# Quectel_BC260Y-CN_SCH_Part_AD_V1_0.net
KiCad netlist of a schematic drawn in Altium Designer
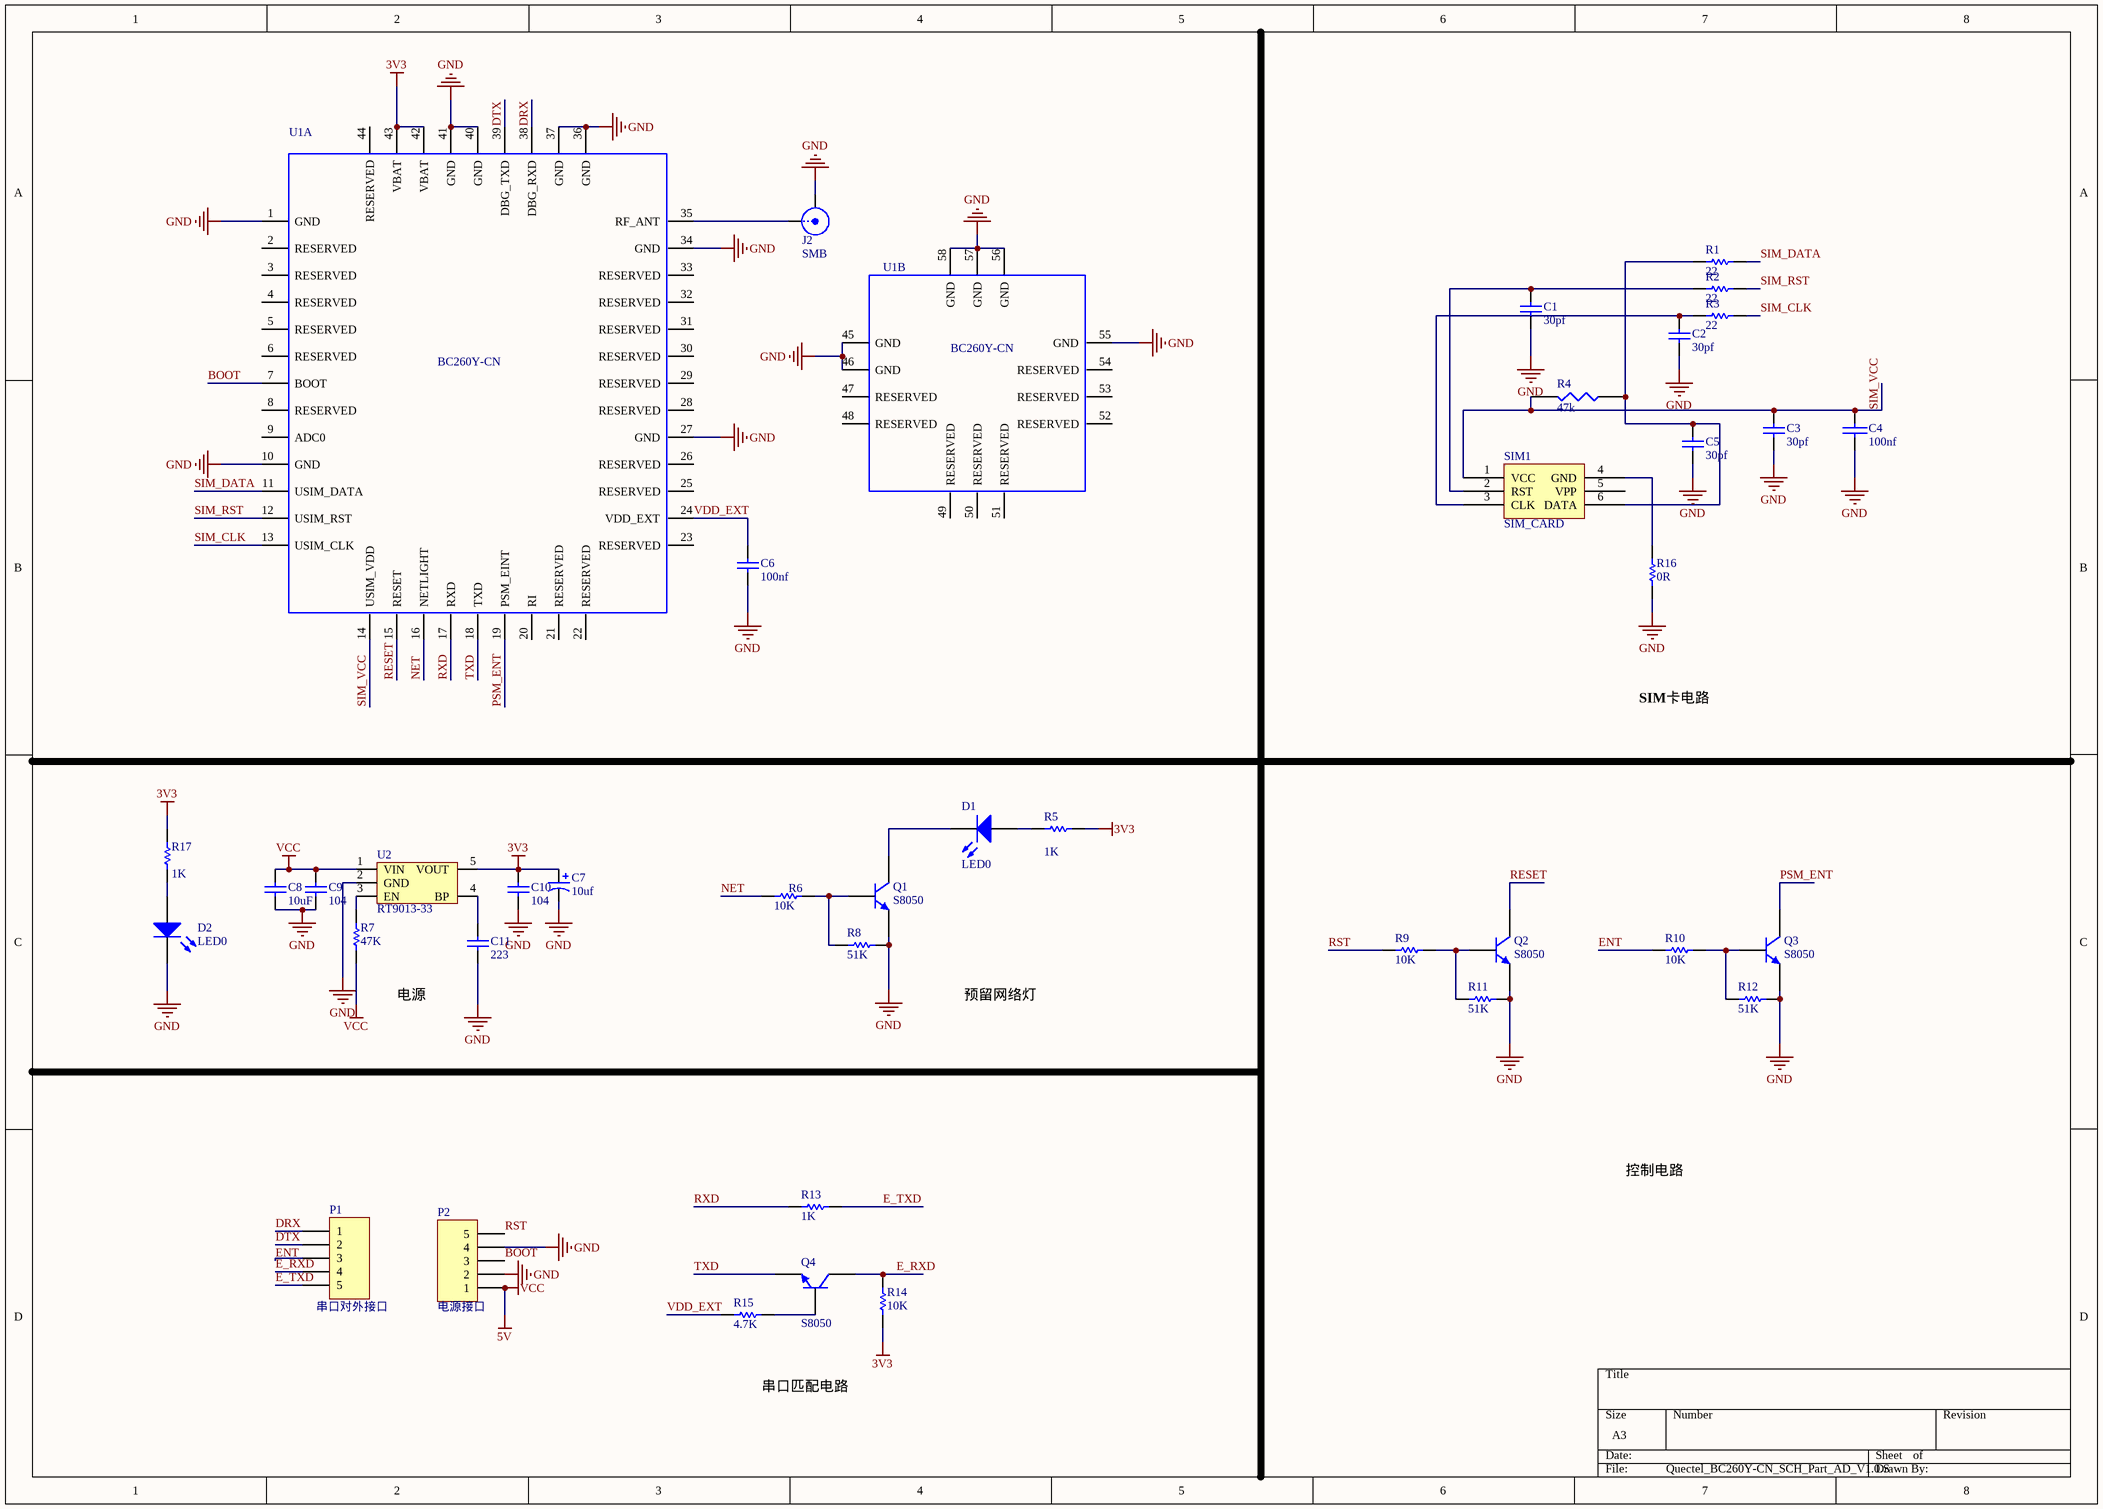
[diagram p0: Quectel_BC260Y-CN_SCH_Part_AD_V1.0.SchDoc]

(export (version "E")
  (design (tool "Eeschema 10.0.6"))
  (components
    (comp (ref "C1")
      (value "30pf")
      (footprint "0603A")
      (description "Capacitor")
      (fields (field (name "PUBLISHER") "Altium Limited"))
      (libsource (lib "Miscellaneous Devices") (part "Cap"))
    )
    (comp (ref "C2")
      (value "30pf")
      (footprint "0603A")
      (description "Capacitor")
      (fields (field (name "PUBLISHER") "Altium Limited"))
      (libsource (lib "Miscellaneous Devices") (part "Cap"))
    )
    (comp (ref "C3")
      (value "30pf")
      (footprint "0603A")
      (description "Capacitor")
      (fields (field (name "PUBLISHER") "Altium Limited"))
      (libsource (lib "Miscellaneous Devices") (part "Cap"))
    )
    (comp (ref "C4")
      (value "100nf")
      (footprint "0603A")
      (description "Capacitor")
      (libsource (lib "Miscellaneous Devices") (part "CAP"))
    )
    (comp (ref "C5")
      (value "30pf")
      (footprint "0603A")
      (description "Capacitor")
      (fields (field (name "PUBLISHER") "Altium Limited"))
      (libsource (lib "Miscellaneous Devices") (part "Cap"))
    )
    (comp (ref "C6")
      (value "100nf")
      (footprint "0603a")
      (description "Capacitor")
      (fields (field (name "PUBLISHER") "Altium Limited"))
      (libsource (lib "Miscellaneous Devices") (part "Cap"))
    )
    (comp (ref "C7") (value "10uf") (footprint "1206") (libsource (lib "*") (part "CAP-POL")))
    (comp (ref "C8")
      (value "10uF")
      (footprint "1206")
      (description "Capacitor")
      (fields (field (name "PUBLISHER") "Altium Limited"))
      (libsource (lib "Miscellaneous Devices") (part "Cap"))
    )
    (comp (ref "C9")
      (value "104")
      (footprint "0603a")
      (description "Capacitor")
      (fields (field (name "PUBLISHER") "Altium Limited"))
      (libsource (lib "Miscellaneous Devices") (part "Cap"))
    )
    (comp (ref "C10")
      (value "104")
      (footprint "0603a")
      (description "Capacitor")
      (fields (field (name "PUBLISHER") "Altium Limited"))
      (libsource (lib "Miscellaneous Devices") (part "Cap"))
    )
    (comp (ref "C11")
      (value "223")
      (footprint "0603a")
      (description "Capacitor")
      (fields (field (name "PUBLISHER") "Altium Limited"))
      (libsource (lib "Miscellaneous Devices") (part "Cap"))
    )
    (comp (ref "D1")
      (value "LED0")
      (footprint "0603led")
      (description "Typical INFRARED GaAs LED")
      (fields (field (name "PUBLISHER") "Altium Limited"))
      (libsource (lib "Miscellaneous Devices") (part "LED0"))
    )
    (comp (ref "D2")
      (value "LED0")
      (footprint "0603led")
      (description "Typical INFRARED GaAs LED")
      (fields (field (name "PUBLISHER") "Altium Limited"))
      (libsource (lib "Miscellaneous Devices") (part "LED0"))
    )
    (comp (ref "J2")
      (value "SMB")
      (footprint "ipex")
      (description "SMB Straight Connector")
      (fields (field (name "PUBLISHER") "Altium Limited"))
      (libsource (lib "Miscellaneous Connectors") (part "SMB"))
    )
    (comp (ref "P1")
      (value "串口对外接口")
      (footprint "HDR1X5")
      (description "Header, 5-Pin")
      (fields (field (name "PUBLISHER") "Altium Limited"))
      (libsource (lib "") (part "Header 5_1"))
    )
    (comp (ref "P2")
      (value "电源接口")
      (footprint "HDR1X5")
      (description "Header, 5-Pin")
      (fields (field (name "PUBLISHER") "Altium Limited"))
      (libsource (lib "Miscellaneous Connectors") (part "Header 5"))
    )
    (comp (ref "Q1")
      (value "S8050")
      (footprint "s8550")
      (description "NPN General Purpose Amplifier")
      (fields (field (name "PUBLISHER") "Altium Limited"))
      (libsource (lib "Miscellaneous Devices") (part "2N3904"))
    )
    (comp (ref "Q2")
      (value "S8050")
      (footprint "s8550")
      (description "NPN General Purpose Amplifier")
      (fields (field (name "PUBLISHER") "Altium Limited"))
      (libsource (lib "Miscellaneous Devices") (part "2N3904"))
    )
    (comp (ref "Q3")
      (value "S8050")
      (footprint "s8550")
      (description "NPN General Purpose Amplifier")
      (fields (field (name "PUBLISHER") "Altium Limited"))
      (libsource (lib "Miscellaneous Devices") (part "2N3904"))
    )
    (comp (ref "Q4")
      (value "S8050")
      (footprint "S8550")
      (description "NPN General Purpose Amplifier")
      (fields (field (name "PUBLISHER") "Altium Limited"))
      (libsource (lib "Miscellaneous Devices") (part "2N3904"))
    )
    (comp (ref "R1")
      (value "22")
      (footprint "0603A")
      (description "Resistor")
      (fields (field (name "PUBLISHER") "Altium Limited"))
      (libsource (lib "Miscellaneous Devices") (part "Res1"))
    )
    (comp (ref "R2")
      (value "22")
      (footprint "0603A")
      (description "Resistor")
      (fields (field (name "PUBLISHER") "Altium Limited"))
      (libsource (lib "Miscellaneous Devices") (part "Res1"))
    )
    (comp (ref "R3")
      (value "22")
      (footprint "0603A")
      (description "Resistor")
      (fields (field (name "PUBLISHER") "Altium Limited"))
      (libsource (lib "Miscellaneous Devices") (part "Res1"))
    )
    (comp (ref "R4")
      (value "47k")
      (footprint "0603A")
      (libsource (lib "Miscellaneous Devices") (part "RES1"))
    )
    (comp (ref "R5")
      (value "1K")
      (footprint "0603a")
      (description "Semiconductor Resistor")
      (fields (field (name "PUBLISHER") "Altium Limited"))
      (libsource (lib "Miscellaneous Devices") (part "Res Semi"))
    )
    (comp (ref "R6")
      (value "10K")
      (footprint "0603A")
      (description "Resistor")
      (fields (field (name "PUBLISHER") "Altium Limited"))
      (libsource (lib "Miscellaneous Devices") (part "Res1"))
    )
    (comp (ref "R7")
      (value "47K")
      (footprint "0603a")
      (description "Resistor")
      (fields (field (name "PUBLISHER") "Altium Limited"))
      (libsource (lib "Miscellaneous Devices") (part "Res1"))
    )
    (comp (ref "R8")
      (value "51K")
      (footprint "0603A")
      (description "Resistor")
      (fields (field (name "PUBLISHER") "Altium Limited"))
      (libsource (lib "Miscellaneous Devices") (part "Res1"))
    )
    (comp (ref "R9")
      (value "10K")
      (footprint "0603A")
      (description "Resistor")
      (fields (field (name "PUBLISHER") "Altium Limited"))
      (libsource (lib "Miscellaneous Devices") (part "Res1"))
    )
    (comp (ref "R10")
      (value "10K")
      (footprint "0603A")
      (description "Resistor")
      (fields (field (name "PUBLISHER") "Altium Limited"))
      (libsource (lib "Miscellaneous Devices") (part "Res1"))
    )
    (comp (ref "R11")
      (value "51K")
      (footprint "0603A")
      (description "Resistor")
      (fields (field (name "PUBLISHER") "Altium Limited"))
      (libsource (lib "Miscellaneous Devices") (part "Res1"))
    )
    (comp (ref "R12")
      (value "51K")
      (footprint "0603A")
      (description "Resistor")
      (fields (field (name "PUBLISHER") "Altium Limited"))
      (libsource (lib "Miscellaneous Devices") (part "Res1"))
    )
    (comp (ref "R13")
      (value "1K")
      (footprint "0603A")
      (description "Resistor")
      (fields (field (name "PUBLISHER") "Altium Limited"))
      (libsource (lib "Miscellaneous Devices") (part "Res1"))
    )
    (comp (ref "R14")
      (value "10K")
      (footprint "0603A")
      (description "Resistor")
      (fields (field (name "PUBLISHER") "Altium Limited"))
      (libsource (lib "Miscellaneous Devices") (part "Res1"))
    )
    (comp (ref "R15")
      (value "4.7K")
      (footprint "0603A")
      (description "Resistor")
      (fields (field (name "PUBLISHER") "Altium Limited"))
      (libsource (lib "Miscellaneous Devices") (part "Res1"))
    )
    (comp (ref "R16")
      (value "0R")
      (footprint "0603A")
      (description "Resistor")
      (fields (field (name "PUBLISHER") "Altium Limited"))
      (libsource (lib "Miscellaneous Devices") (part "Res1"))
    )
    (comp (ref "R17")
      (value "1K")
      (footprint "0603a")
      (description "Semiconductor Resistor")
      (fields (field (name "PUBLISHER") "Altium Limited"))
      (libsource (lib "Miscellaneous Devices") (part "Res Semi"))
    )
    (comp (ref "SIM1")
      (value "SIM_CARD")
      (footprint "microSIMauto")
      (libsource (lib "M26_SCH_140527") (part "SIM_CARD"))
    )
    (comp (ref "U1")
      (value "BC260Y-CN")
      (footprint "bc260y")
      (fields (field (name "MANUFACTURER") "QUECTEL"))
      (libsource (lib "BC260Y-CN") (part "BC260Y-CN"))
    )
    (comp (ref "U2")
      (value "RT9013-33")
      (footprint "SOT-23-5")
      (description "3.3V超低压差LDO")
      (libsource (lib "BC05") (part "RT9193-33"))
    )
  )
  (nets
    (net (code "1") (name "/BOOT") (class "Default")
      (node (ref "P2") (pin "3") (pinfunction "3_3") (pintype "passive"))
      (node (ref "U1") (pin "7") (pinfunction "BOOT_7") (pintype "passive"))
    )
    (net (code "2") (name "/DRX") (class "Default")
      (node (ref "P1") (pin "1") (pinfunction "1_1") (pintype "passive"))
      (node (ref "U1") (pin "38") (pinfunction "DBG_RXD_38") (pintype "passive"))
    )
    (net (code "3") (name "/DTX") (class "Default")
      (node (ref "P1") (pin "2") (pinfunction "2_2") (pintype "passive"))
      (node (ref "U1") (pin "39") (pinfunction "DBG_TXD_39") (pintype "passive"))
    )
    (net (code "4") (name "/ENT") (class "Default")
      (node (ref "P1") (pin "3") (pinfunction "3_3") (pintype "passive"))
      (node (ref "R10") (pin "1") (pinfunction "1_1") (pintype "passive"))
    )
    (net (code "5") (name "/E_RXD") (class "Default")
      (node (ref "P1") (pin "4") (pinfunction "4_4") (pintype "passive"))
      (node (ref "Q4") (pin "3") (pinfunction "C_3") (pintype "passive"))
      (node (ref "R14") (pin "2") (pinfunction "2_2") (pintype "passive"))
    )
    (net (code "6") (name "/E_TXD") (class "Default")
      (node (ref "P1") (pin "5") (pinfunction "5_5") (pintype "passive"))
      (node (ref "R13") (pin "2") (pinfunction "2_2") (pintype "passive"))
    )
    (net (code "7") (name "/NET") (class "Default")
      (node (ref "R6") (pin "1") (pinfunction "1_1") (pintype "passive"))
      (node (ref "U1") (pin "16") (pinfunction "NETLIGHT_16") (pintype "passive"))
    )
    (net (code "8") (name "/PSM_ENT") (class "Default")
      (node (ref "Q3") (pin "3") (pinfunction "C_3") (pintype "passive"))
      (node (ref "U1") (pin "19") (pinfunction "PSM_EINT_19") (pintype "passive"))
    )
    (net (code "9") (name "/RESET") (class "Default")
      (node (ref "Q2") (pin "3") (pinfunction "C_3") (pintype "passive"))
      (node (ref "U1") (pin "15") (pinfunction "RESET_15") (pintype "passive"))
    )
    (net (code "10") (name "/RST") (class "Default")
      (node (ref "P2") (pin "5") (pinfunction "5_5") (pintype "passive"))
      (node (ref "R9") (pin "1") (pinfunction "1_1") (pintype "passive"))
    )
    (net (code "11") (name "/RXD") (class "Default")
      (node (ref "R13") (pin "1") (pinfunction "1_1") (pintype "passive"))
      (node (ref "U1") (pin "17") (pinfunction "RXD_17") (pintype "passive"))
    )
    (net (code "12") (name "/SIM_CLK") (class "Default")
      (node (ref "R3") (pin "1") (pinfunction "1_1") (pintype "passive"))
      (node (ref "U1") (pin "13") (pinfunction "USIM_CLK_13") (pintype "passive"))
    )
    (net (code "13") (name "/SIM_DATA") (class "Default")
      (node (ref "R1") (pin "1") (pinfunction "1_1") (pintype "passive"))
      (node (ref "U1") (pin "11") (pinfunction "USIM_DATA_11") (pintype "passive"))
    )
    (net (code "14") (name "/SIM_RST") (class "Default")
      (node (ref "R2") (pin "1") (pinfunction "1_1") (pintype "passive"))
      (node (ref "U1") (pin "12") (pinfunction "USIM_RST_12") (pintype "passive"))
    )
    (net (code "15") (name "/SIM_VCC") (class "Default")
      (node (ref "C3") (pin "2") (pinfunction "2_2") (pintype "passive"))
      (node (ref "C4") (pin "1") (pinfunction "1_1") (pintype "passive"))
      (node (ref "R4") (pin "2") (pinfunction "2_2") (pintype "passive"))
      (node (ref "SIM1") (pin "1") (pinfunction "VCC_1") (pintype "passive"))
      (node (ref "U1") (pin "14") (pinfunction "USIM_VDD_14") (pintype "passive"))
    )
    (net (code "16") (name "/TXD") (class "Default")
      (node (ref "Q4") (pin "1") (pinfunction "E_1") (pintype "passive"))
      (node (ref "U1") (pin "18") (pinfunction "TXD_18") (pintype "passive"))
    )
    (net (code "17") (name "/VDD_EXT") (class "Default")
      (node (ref "C6") (pin "2") (pinfunction "2_2") (pintype "passive"))
      (node (ref "R15") (pin "1") (pinfunction "1_1") (pintype "passive"))
      (node (ref "U1") (pin "24") (pinfunction "VDD_EXT_24") (pintype "passive"))
    )
    (net (code "18") (name "3V3") (class "Default")
      (node (ref "C10") (pin "1") (pinfunction "1_1") (pintype "passive"))
      (node (ref "C7") (pin "1") (pinfunction "+_1") (pintype "passive"))
      (node (ref "R14") (pin "1") (pinfunction "1_1") (pintype "passive"))
      (node (ref "R17") (pin "1") (pinfunction "1_1") (pintype "passive"))
      (node (ref "R5") (pin "1") (pinfunction "1_1") (pintype "passive"))
      (node (ref "U1") (pin "42") (pinfunction "VBAT_42") (pintype "passive"))
      (node (ref "U1") (pin "43") (pinfunction "VBAT_43") (pintype "passive"))
      (node (ref "U2") (pin "5") (pinfunction "VOUT_5") (pintype "passive"))
    )
    (net (code "19") (name "5V") (class "Default")
      (node (ref "C8") (pin "2") (pinfunction "2_2") (pintype "passive"))
      (node (ref "C9") (pin "2") (pinfunction "2_2") (pintype "passive"))
      (node (ref "P2") (pin "1") (pinfunction "1_1") (pintype "passive"))
      (node (ref "R7") (pin "1") (pinfunction "1_1") (pintype "passive"))
      (node (ref "U2") (pin "1") (pinfunction "VIN_1") (pintype "passive"))
    )
    (net (code "20") (name "GND") (class "Default")
      (node (ref "C1") (pin "1") (pinfunction "1_1") (pintype "passive"))
      (node (ref "C10") (pin "2") (pinfunction "2_2") (pintype "passive"))
      (node (ref "C11") (pin "2") (pinfunction "2_2") (pintype "passive"))
      (node (ref "C2") (pin "1") (pinfunction "1_1") (pintype "passive"))
      (node (ref "C3") (pin "1") (pinfunction "1_1") (pintype "passive"))
      (node (ref "C4") (pin "2") (pinfunction "2_2") (pintype "passive"))
      (node (ref "C5") (pin "1") (pinfunction "1_1") (pintype "passive"))
      (node (ref "C6") (pin "1") (pinfunction "1_1") (pintype "passive"))
      (node (ref "C7") (pin "2") (pinfunction "-_2") (pintype "passive"))
      (node (ref "C8") (pin "1") (pinfunction "1_1") (pintype "passive"))
      (node (ref "C9") (pin "1") (pinfunction "1_1") (pintype "passive"))
      (node (ref "D2") (pin "2") (pinfunction "K_2") (pintype "passive"))
      (node (ref "J2") (pin "2") (pinfunction "Y_2") (pintype "passive"))
      (node (ref "P2") (pin "2") (pinfunction "2_2") (pintype "passive"))
      (node (ref "P2") (pin "4") (pinfunction "4_4") (pintype "passive"))
      (node (ref "Q1") (pin "1") (pinfunction "E_1") (pintype "passive"))
      (node (ref "Q2") (pin "1") (pinfunction "E_1") (pintype "passive"))
      (node (ref "Q3") (pin "1") (pinfunction "E_1") (pintype "passive"))
      (node (ref "R11") (pin "2") (pinfunction "2_2") (pintype "passive"))
      (node (ref "R12") (pin "2") (pinfunction "2_2") (pintype "passive"))
      (node (ref "R16") (pin "1") (pinfunction "1_1") (pintype "passive"))
      (node (ref "R8") (pin "2") (pinfunction "2_2") (pintype "passive"))
      (node (ref "U1") (pin "1") (pinfunction "GND_1") (pintype "passive"))
      (node (ref "U1") (pin "10") (pinfunction "GND_10") (pintype "passive"))
      (node (ref "U1") (pin "27") (pinfunction "GND_27") (pintype "passive"))
      (node (ref "U1") (pin "34") (pinfunction "GND_34") (pintype "passive"))
      (node (ref "U1") (pin "36") (pinfunction "GND_36") (pintype "passive"))
      (node (ref "U1") (pin "37") (pinfunction "GND_37") (pintype "passive"))
      (node (ref "U1") (pin "40") (pinfunction "GND_40") (pintype "passive"))
      (node (ref "U1") (pin "41") (pinfunction "GND_41") (pintype "passive"))
      (node (ref "U1") (pin "45") (pinfunction "GND_45") (pintype "passive"))
      (node (ref "U1") (pin "46") (pinfunction "GND_46") (pintype "passive"))
      (node (ref "U1") (pin "55") (pinfunction "GND_55") (pintype "passive"))
      (node (ref "U1") (pin "56") (pinfunction "GND_56") (pintype "passive"))
      (node (ref "U1") (pin "57") (pinfunction "GND_57") (pintype "passive"))
      (node (ref "U1") (pin "58") (pinfunction "GND_58") (pintype "passive"))
      (node (ref "U2") (pin "2") (pinfunction "GND_2") (pintype "passive"))
    )
    (net (code "21") (name "Net-(D1-A)") (class "Default")
      (node (ref "D1") (pin "1") (pinfunction "A_1") (pintype "passive"))
      (node (ref "R5") (pin "2") (pinfunction "2_2") (pintype "passive"))
    )
    (net (code "22") (name "Net-(D1-K)") (class "Default")
      (node (ref "D1") (pin "2") (pinfunction "K_2") (pintype "passive"))
      (node (ref "Q1") (pin "3") (pinfunction "C_3") (pintype "passive"))
    )
    (net (code "23") (name "Net-(D2-A)") (class "Default")
      (node (ref "D2") (pin "1") (pinfunction "A_1") (pintype "passive"))
      (node (ref "R17") (pin "2") (pinfunction "2_2") (pintype "passive"))
    )
    (net (code "24") (name "Net-(J2-X)") (class "Default")
      (node (ref "J2") (pin "1") (pinfunction "X_1") (pintype "passive"))
      (node (ref "U1") (pin "35") (pinfunction "RF_ANT_35") (pintype "passive"))
    )
    (net (code "25") (name "Net-(Q1-B)") (class "Default")
      (node (ref "Q1") (pin "2") (pinfunction "B_2") (pintype "passive"))
      (node (ref "R6") (pin "2") (pinfunction "2_2") (pintype "passive"))
      (node (ref "R8") (pin "1") (pinfunction "1_1") (pintype "passive"))
    )
    (net (code "26") (name "Net-(Q2-B)") (class "Default")
      (node (ref "Q2") (pin "2") (pinfunction "B_2") (pintype "passive"))
      (node (ref "R11") (pin "1") (pinfunction "1_1") (pintype "passive"))
      (node (ref "R9") (pin "2") (pinfunction "2_2") (pintype "passive"))
    )
    (net (code "27") (name "Net-(Q3-B)") (class "Default")
      (node (ref "Q3") (pin "2") (pinfunction "B_2") (pintype "passive"))
      (node (ref "R10") (pin "2") (pinfunction "2_2") (pintype "passive"))
      (node (ref "R12") (pin "1") (pinfunction "1_1") (pintype "passive"))
    )
    (net (code "28") (name "Net-(Q4-B)") (class "Default")
      (node (ref "Q4") (pin "2") (pinfunction "B_2") (pintype "passive"))
      (node (ref "R15") (pin "2") (pinfunction "2_2") (pintype "passive"))
    )
    (net (code "29") (name "Net-(SIM1-CLK)") (class "Default")
      (node (ref "C2") (pin "2") (pinfunction "2_2") (pintype "passive"))
      (node (ref "R3") (pin "2") (pinfunction "2_2") (pintype "passive"))
      (node (ref "SIM1") (pin "3") (pinfunction "CLK_3") (pintype "passive"))
    )
    (net (code "30") (name "Net-(SIM1-DATA)") (class "Default")
      (node (ref "C5") (pin "2") (pinfunction "2_2") (pintype "passive"))
      (node (ref "R1") (pin "2") (pinfunction "2_2") (pintype "passive"))
      (node (ref "R4") (pin "1") (pinfunction "1_1") (pintype "passive"))
      (node (ref "SIM1") (pin "6") (pinfunction "DATA_6") (pintype "passive"))
    )
    (net (code "31") (name "Net-(SIM1-GND)") (class "Default")
      (node (ref "R16") (pin "2") (pinfunction "2_2") (pintype "passive"))
      (node (ref "SIM1") (pin "4") (pinfunction "GND_4") (pintype "passive"))
    )
    (net (code "32") (name "Net-(SIM1-RST)") (class "Default")
      (node (ref "C1") (pin "2") (pinfunction "2_2") (pintype "passive"))
      (node (ref "R2") (pin "2") (pinfunction "2_2") (pintype "passive"))
      (node (ref "SIM1") (pin "2") (pinfunction "RST_2") (pintype "passive"))
    )
    (net (code "33") (name "Net-(U2-BP)") (class "Default")
      (node (ref "C11") (pin "1") (pinfunction "1_1") (pintype "passive"))
      (node (ref "U2") (pin "4") (pinfunction "BP_4") (pintype "passive"))
    )
    (net (code "34") (name "Net-(U2-EN)") (class "Default")
      (node (ref "R7") (pin "2") (pinfunction "2_2") (pintype "passive"))
      (node (ref "U2") (pin "3") (pinfunction "EN_3") (pintype "passive"))
    )
    (net (code "35") (name "unconnected-(SIM1-VPP-Pad5)") (class "Default")
      (node (ref "SIM1") (pin "5") (pinfunction "VPP_5") (pintype "passive"))
    )
    (net (code "36") (name "unconnected-(U1A-ADC0-Pad9)") (class "Default")
      (node (ref "U1") (pin "9") (pinfunction "ADC0_9") (pintype "passive"))
    )
    (net (code "37") (name "unconnected-(U1A-RESERVED-Pad2)") (class "Default")
      (node (ref "U1") (pin "2") (pinfunction "RESERVED_2") (pintype "passive"))
    )
    (net (code "38") (name "unconnected-(U1A-RESERVED-Pad3)") (class "Default")
      (node (ref "U1") (pin "3") (pinfunction "RESERVED_3") (pintype "passive"))
    )
    (net (code "39") (name "unconnected-(U1A-RESERVED-Pad4)") (class "Default")
      (node (ref "U1") (pin "4") (pinfunction "RESERVED_4") (pintype "passive"))
    )
    (net (code "40") (name "unconnected-(U1A-RESERVED-Pad5)") (class "Default")
      (node (ref "U1") (pin "5") (pinfunction "RESERVED_5") (pintype "passive"))
    )
    (net (code "41") (name "unconnected-(U1A-RESERVED-Pad6)") (class "Default")
      (node (ref "U1") (pin "6") (pinfunction "RESERVED_6") (pintype "passive"))
    )
    (net (code "42") (name "unconnected-(U1A-RESERVED-Pad8)") (class "Default")
      (node (ref "U1") (pin "8") (pinfunction "RESERVED_8") (pintype "passive"))
    )
    (net (code "43") (name "unconnected-(U1A-RESERVED-Pad21)") (class "Default")
      (node (ref "U1") (pin "21") (pinfunction "RESERVED_21") (pintype "passive"))
    )
    (net (code "44") (name "unconnected-(U1A-RESERVED-Pad22)") (class "Default")
      (node (ref "U1") (pin "22") (pinfunction "RESERVED_22") (pintype "passive"))
    )
    (net (code "45") (name "unconnected-(U1A-RESERVED-Pad23)") (class "Default")
      (node (ref "U1") (pin "23") (pinfunction "RESERVED_23") (pintype "passive"))
    )
    (net (code "46") (name "unconnected-(U1A-RESERVED-Pad25)") (class "Default")
      (node (ref "U1") (pin "25") (pinfunction "RESERVED_25") (pintype "passive"))
    )
    (net (code "47") (name "unconnected-(U1A-RESERVED-Pad26)") (class "Default")
      (node (ref "U1") (pin "26") (pinfunction "RESERVED_26") (pintype "passive"))
    )
    (net (code "48") (name "unconnected-(U1A-RESERVED-Pad28)") (class "Default")
      (node (ref "U1") (pin "28") (pinfunction "RESERVED_28") (pintype "passive"))
    )
    (net (code "49") (name "unconnected-(U1A-RESERVED-Pad29)") (class "Default")
      (node (ref "U1") (pin "29") (pinfunction "RESERVED_29") (pintype "passive"))
    )
    (net (code "50") (name "unconnected-(U1A-RESERVED-Pad30)") (class "Default")
      (node (ref "U1") (pin "30") (pinfunction "RESERVED_30") (pintype "passive"))
    )
    (net (code "51") (name "unconnected-(U1A-RESERVED-Pad31)") (class "Default")
      (node (ref "U1") (pin "31") (pinfunction "RESERVED_31") (pintype "passive"))
    )
    (net (code "52") (name "unconnected-(U1A-RESERVED-Pad32)") (class "Default")
      (node (ref "U1") (pin "32") (pinfunction "RESERVED_32") (pintype "passive"))
    )
    (net (code "53") (name "unconnected-(U1A-RESERVED-Pad33)") (class "Default")
      (node (ref "U1") (pin "33") (pinfunction "RESERVED_33") (pintype "passive"))
    )
    (net (code "54") (name "unconnected-(U1A-RESERVED-Pad44)") (class "Default")
      (node (ref "U1") (pin "44") (pinfunction "RESERVED_44") (pintype "passive"))
    )
    (net (code "55") (name "unconnected-(U1A-RI-Pad20)") (class "Default")
      (node (ref "U1") (pin "20") (pinfunction "RI_20") (pintype "passive"))
    )
    (net (code "56") (name "unconnected-(U1B-RESERVED-Pad47)") (class "Default")
      (node (ref "U1") (pin "47") (pinfunction "RESERVED_47") (pintype "passive"))
    )
    (net (code "57") (name "unconnected-(U1B-RESERVED-Pad48)") (class "Default")
      (node (ref "U1") (pin "48") (pinfunction "RESERVED_48") (pintype "passive"))
    )
    (net (code "58") (name "unconnected-(U1B-RESERVED-Pad49)") (class "Default")
      (node (ref "U1") (pin "49") (pinfunction "RESERVED_49") (pintype "passive"))
    )
    (net (code "59") (name "unconnected-(U1B-RESERVED-Pad50)") (class "Default")
      (node (ref "U1") (pin "50") (pinfunction "RESERVED_50") (pintype "passive"))
    )
    (net (code "60") (name "unconnected-(U1B-RESERVED-Pad51)") (class "Default")
      (node (ref "U1") (pin "51") (pinfunction "RESERVED_51") (pintype "passive"))
    )
    (net (code "61") (name "unconnected-(U1B-RESERVED-Pad52)") (class "Default")
      (node (ref "U1") (pin "52") (pinfunction "RESERVED_52") (pintype "passive"))
    )
    (net (code "62") (name "unconnected-(U1B-RESERVED-Pad53)") (class "Default")
      (node (ref "U1") (pin "53") (pinfunction "RESERVED_53") (pintype "passive"))
    )
    (net (code "63") (name "unconnected-(U1B-RESERVED-Pad54)") (class "Default")
      (node (ref "U1") (pin "54") (pinfunction "RESERVED_54") (pintype "passive"))
    )
  )
)
